# Power.net
KiCad netlist of a schematic drawn in Altium Designer
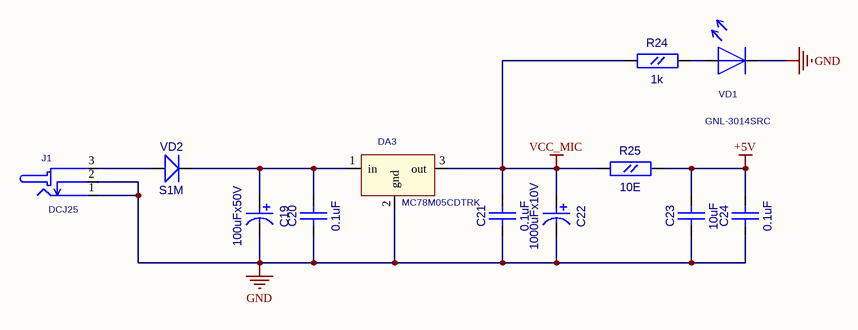
[diagram p0: Power.SchDoc]

(export (version "E")
  (design (tool "Eeschema 10.0.6"))
  (components
    (comp (ref "C19")
      (value "100uFx50V")
      (footprint "CC8X3.5")
      (description "CAP0.35")
      (libsource (lib "gprs_modem_2") (part "CAP0.35"))
    )
    (comp (ref "C20")
      (value "0.1uF")
      (footprint "CC0603")
      (description "CC0603")
      (libsource (lib "gprs_modem_2") (part "CC0603"))
    )
    (comp (ref "C21")
      (value "0.1uF")
      (footprint "CC0603")
      (description "CC0603")
      (libsource (lib "gprs_modem_2") (part "CC0603"))
    )
    (comp (ref "C22")
      (value "1000uFx10V")
      (footprint "CC8X3.5")
      (description "CAP0.35")
      (libsource (lib "gprs_modem_2") (part "CAP0.35"))
    )
    (comp (ref "C23")
      (value "10uF")
      (footprint "CC0805")
      (description "CC0805")
      (libsource (lib "gprs_modem_2") (part "CC0805"))
    )
    (comp (ref "C24")
      (value "0.1uF")
      (footprint "CC0603")
      (description "CC0603")
      (libsource (lib "gprs_modem_2") (part "CC0603"))
    )
    (comp (ref "DA3")
      (value "MC78M05CDTRK")
      (footprint "D-PAK(TO-252AA)")
      (libsource (lib "gprs_modem_2") (part "MC78M05CDTRK"))
    )
    (comp (ref "J1") (value "DCJ25") (footprint "DCJ25") (libsource (lib "gprs_modem_2") (part "DCJ25")))
    (comp (ref "R24")
      (value "1k")
      (footprint "RC0603")
      (description "RC0603")
      (libsource (lib "gprs_modem_2") (part "RC0603"))
    )
    (comp (ref "R25")
      (value "10E")
      (footprint "RC0805")
      (description "RC0805")
      (libsource (lib "gprs_modem_2") (part "RC0805"))
    )
    (comp (ref "VD1")
      (value "GNL-3014SRC")
      (footprint "LED3")
      (description "LED_3")
      (libsource (lib "gprs_modem_2") (part "LED_3"))
    )
    (comp (ref "VD2")
      (value "S1M")
      (footprint "SMA")
      (description "Schottky Rectifier")
      (libsource (lib "gprs_modem_2") (part "SS14"))
    )
  )
  (nets
    (net (code "1") (name "+5V") (class "Default")
      (node (ref "C23") (pin "2") (pinfunction "B_2") (pintype "passive"))
      (node (ref "C24") (pin "2") (pinfunction "B_2") (pintype "passive"))
      (node (ref "R25") (pin "2") (pinfunction "B_2") (pintype "passive"))
    )
    (net (code "2") (name "GND") (class "Default")
      (node (ref "C19") (pin "2") (pintype "passive"))
      (node (ref "C20") (pin "1") (pinfunction "A_1") (pintype "passive"))
      (node (ref "C21") (pin "1") (pinfunction "A_1") (pintype "passive"))
      (node (ref "C22") (pin "2") (pintype "passive"))
      (node (ref "C23") (pin "1") (pinfunction "A_1") (pintype "passive"))
      (node (ref "C24") (pin "1") (pinfunction "A_1") (pintype "passive"))
      (node (ref "DA3") (pin "2") (pinfunction "gnd_2") (pintype "passive"))
      (node (ref "J1") (pin "1") (pintype "passive"))
      (node (ref "J1") (pin "2") (pintype "passive"))
      (node (ref "VD1") (pin "1") (pintype "passive"))
    )
    (net (code "3") (name "Net-(C20-B)") (class "Default")
      (node (ref "C19") (pin "1") (pintype "passive"))
      (node (ref "C20") (pin "2") (pinfunction "B_2") (pintype "passive"))
      (node (ref "DA3") (pin "1") (pinfunction "in_1") (pintype "passive"))
      (node (ref "VD2") (pin "2") (pinfunction "K_2") (pintype "passive"))
    )
    (net (code "4") (name "Net-(R24-B)") (class "Default")
      (node (ref "R24") (pin "2") (pinfunction "B_2") (pintype "passive"))
      (node (ref "VD1") (pin "2") (pintype "passive"))
    )
    (net (code "5") (name "Net-(VD2-A)") (class "Default")
      (node (ref "J1") (pin "3") (pintype "passive"))
      (node (ref "VD2") (pin "1") (pinfunction "A_1") (pintype "passive"))
    )
    (net (code "6") (name "VCC_MIC") (class "Default")
      (node (ref "C21") (pin "2") (pinfunction "B_2") (pintype "passive"))
      (node (ref "C22") (pin "1") (pintype "passive"))
      (node (ref "DA3") (pin "3") (pinfunction "out_3") (pintype "passive"))
      (node (ref "R24") (pin "1") (pinfunction "A_1") (pintype "passive"))
      (node (ref "R25") (pin "1") (pinfunction "A_1") (pintype "passive"))
    )
  )
)
